# MRCS-ATSN.net
KiCad netlist of a schematic drawn in EAGLE
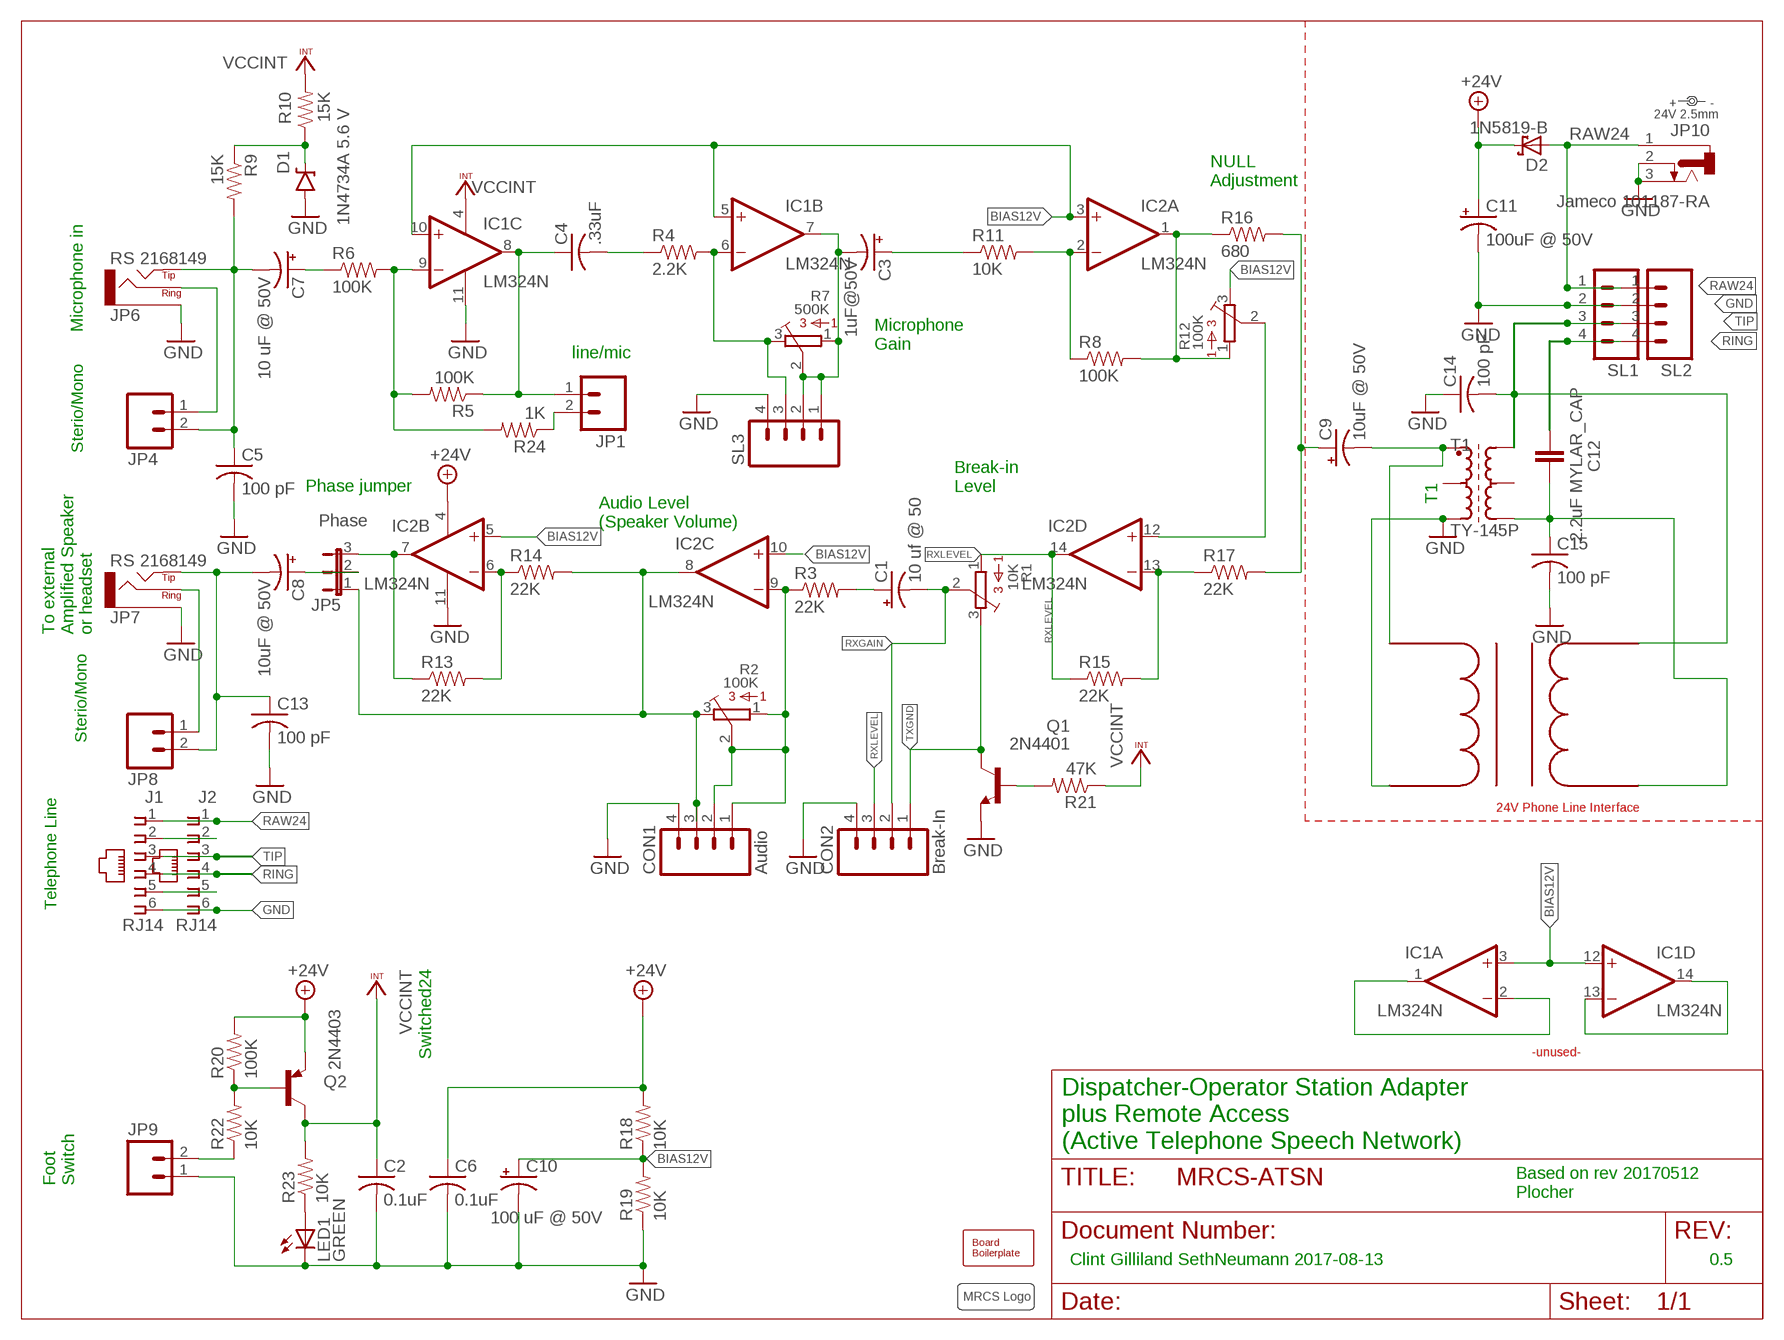
[diagram p0: schematic, sheet 1]

(export (version "E")
  (design (tool "Eeschema 10.0.6"))
  (components
    (comp (ref "BOARD1")
      (value "BOARD69X100")
      (footprint "eagle-import:BOARD-DINRAIL-2.7IN-16CM")
      (libsource (lib "eagle-import") (part "BOARD69X160"))
    )
    (comp (ref "C1")
      (value "10 uf @ 50")
      (footprint "eagle-import:E2-5")
      (libsource (lib "eagle-import") (part "CPOL-USE2-5"))
    )
    (comp (ref "C2")
      (value "0.1uF")
      (footprint "eagle-import:C025-030X050")
      (libsource (lib "eagle-import") (part "C-US025-030X050"))
    )
    (comp (ref "C3")
      (value "1uF@50V")
      (footprint "eagle-import:E2-5")
      (libsource (lib "eagle-import") (part "CPOL-USE2-5"))
    )
    (comp (ref "C4")
      (value ".33uF")
      (footprint "eagle-import:C050-050X075")
      (libsource (lib "eagle-import") (part "C-US050-050X075"))
    )
    (comp (ref "C5")
      (value "100 pF")
      (footprint "eagle-import:C050-025X075")
      (libsource (lib "eagle-import") (part "C-US050-025X075"))
    )
    (comp (ref "C6")
      (value "0.1uF")
      (footprint "eagle-import:C025-030X050")
      (libsource (lib "eagle-import") (part "C-US025-030X050"))
    )
    (comp (ref "C7")
      (value "10 uF @ 50V")
      (footprint "eagle-import:E2-5")
      (libsource (lib "eagle-import") (part "CPOL-USE2-5"))
    )
    (comp (ref "C8")
      (value "10uF @ 50V")
      (footprint "eagle-import:E2-5")
      (libsource (lib "eagle-import") (part "CPOL-USE2-5"))
    )
    (comp (ref "C9")
      (value "10uF @ 50V")
      (footprint "eagle-import:E2-5")
      (libsource (lib "eagle-import") (part "CPOL-USE2-5"))
    )
    (comp (ref "C10")
      (value "100 uF @ 50V")
      (footprint "eagle-import:E3.5-10")
      (libsource (lib "eagle-import") (part "CPOL-USE3.5-10"))
    )
    (comp (ref "C11")
      (value "100uF @ 50V")
      (footprint "eagle-import:E3.5-10")
      (libsource (lib "eagle-import") (part "CPOL-USE3.5-10"))
    )
    (comp (ref "C12")
      (value "2.2uF MYLAR_CAP")
      (footprint "eagle-import:C15B9")
      (libsource (lib "eagle-import") (part "C15/9"))
    )
    (comp (ref "C13")
      (value "100 pF")
      (footprint "eagle-import:C050-025X075")
      (libsource (lib "eagle-import") (part "C-US050-025X075"))
    )
    (comp (ref "C14")
      (value "100 pF")
      (footprint "eagle-import:C025-030X050")
      (libsource (lib "eagle-import") (part "C-US025-030X050"))
    )
    (comp (ref "C15")
      (value "100 pF")
      (footprint "eagle-import:C025-030X050")
      (libsource (lib "eagle-import") (part "C-US025-030X050"))
    )
    (comp (ref "CON1")
      (value "Audio")
      (footprint "eagle-import:1X04_LOCK")
      (libsource (lib "eagle-import") (part "SPCoast 2017_04_CONNECTOR-M04LOCK"))
    )
    (comp (ref "CON2")
      (value "Break-In")
      (footprint "eagle-import:1X04_LOCK")
      (libsource (lib "eagle-import") (part "SPCoast 2017_04_CONNECTOR-M04LOCK"))
    )
    (comp (ref "D1")
      (value "1N4734A 5.6 V")
      (footprint "eagle-import:DIODE-ZENER")
      (libsource (lib "eagle-import") (part "DIODE-ZENERPTH"))
    )
    (comp (ref "D2")
      (value "1N5819-B")
      (footprint "eagle-import:DO41-7.6")
      (libsource (lib "eagle-import") (part "1N5819-B"))
    )
    (comp (ref "IC1")
      (value "LM324N")
      (footprint "eagle-import:DIL14")
      (libsource (lib "eagle-import") (part "LM324N"))
    )
    (comp (ref "IC2")
      (value "LM324N")
      (footprint "eagle-import:DIL14")
      (libsource (lib "eagle-import") (part "LM324N"))
    )
    (comp (ref "J1")
      (value "RJ14")
      (footprint "eagle-import:RJ25-INVERTED")
      (libsource (lib "eagle-import") (part "CONNECTOR-RJ25-43860-2-MOLEX"))
    )
    (comp (ref "J2")
      (value "RJ14")
      (footprint "eagle-import:RJ25-INVERTED")
      (libsource (lib "eagle-import") (part "CONNECTOR-RJ25-43860-2-MOLEX"))
    )
    (comp (ref "JP1")
      (value "CONNECTOR-M021X02-LOCK")
      (footprint "eagle-import:1X02_LOCK")
      (libsource (lib "eagle-import") (part "CONNECTOR-M021X02-LOCK"))
    )
    (comp (ref "JP4")
      (value "CONNECTOR-M021X02-LOCK")
      (footprint "eagle-import:1X02_LOCK")
      (libsource (lib "eagle-import") (part "CONNECTOR-M021X02-LOCK"))
    )
    (comp (ref "JP5")
      (value "Phase")
      (footprint "eagle-import:1X03")
      (libsource (lib "eagle-import") (part "JUMPER-3PTH-LOCK"))
    )
    (comp (ref "JP6")
      (value "RS 2168149")
      (footprint "eagle-import:AUDIO-JACK-3.5MM_STEREO")
      (libsource (lib "eagle-import") (part "CONNECTOR-AUDIO3.5MM-ADAMTECH"))
    )
    (comp (ref "JP7")
      (value "RS 2168149")
      (footprint "eagle-import:AUDIO-JACK-3.5MM_STEREO")
      (libsource (lib "eagle-import") (part "CONNECTOR-AUDIO3.5MM-ADAMTECH"))
    )
    (comp (ref "JP8")
      (value "CONNECTOR-M021X02-LOCK")
      (footprint "eagle-import:1X02_LOCK")
      (libsource (lib "eagle-import") (part "CONNECTOR-M021X02-LOCK"))
    )
    (comp (ref "JP9")
      (value "CONNECTOR-M02508-LOCK")
      (footprint "eagle-import:MSTB2")
      (libsource (lib "eagle-import") (part "CONNECTOR-M02508-LOCK"))
    )
    (comp (ref "JP10")
      (value "Jameco 101187-RA")
      (footprint "eagle-import:DCJ0202")
      (libsource (lib "eagle-import") (part "CONNECTOR-DC-POWER-RA"))
    )
    (comp (ref "LED1")
      (value "GREEN")
      (footprint "eagle-import:LED3MM")
      (libsource (lib "eagle-import") (part "LED3MM"))
    )
    (comp (ref "POWER")
      (value "24V 2.5mm")
      (footprint "eagle-import:POWER_USAGE")
      (libsource (lib "eagle-import") (part "DOC-POWER_LABEL"))
    )
    (comp (ref "Q1")
      (value "2N4401")
      (footprint "eagle-import:TO92-EBC")
      (libsource (lib "eagle-import") (part "-NPN-TO92-EBC29"))
    )
    (comp (ref "Q2")
      (value "2N4403")
      (footprint "eagle-import:TO92-CBE")
      (libsource (lib "eagle-import") (part "2N4126"))
    )
    (comp (ref "R1")
      (value "10K")
      (footprint "eagle-import:3386K")
      (libsource (lib "eagle-import") (part "3386-K"))
    )
    (comp (ref "R2")
      (value "100K")
      (footprint "eagle-import:3386K")
      (libsource (lib "eagle-import") (part "3386-K"))
    )
    (comp (ref "R3")
      (value "22K")
      (footprint "eagle-import:AXIAL-0.4")
      (libsource (lib "eagle-import") (part "RESISTORPTH-1/4W"))
    )
    (comp (ref "R4")
      (value "2.2K")
      (footprint "eagle-import:AXIAL-0.4")
      (libsource (lib "eagle-import") (part "RESISTORPTH-1/4W"))
    )
    (comp (ref "R5")
      (value "100K")
      (footprint "eagle-import:AXIAL-0.4")
      (libsource (lib "eagle-import") (part "RESISTORPTH-1/4W"))
    )
    (comp (ref "R6")
      (value "100K")
      (footprint "eagle-import:AXIAL-0.4")
      (libsource (lib "eagle-import") (part "RESISTORPTH-1/4W"))
    )
    (comp (ref "R7")
      (value "500K")
      (footprint "eagle-import:3386K")
      (libsource (lib "eagle-import") (part "3386-K"))
    )
    (comp (ref "R8")
      (value "100K")
      (footprint "eagle-import:AXIAL-0.4")
      (libsource (lib "eagle-import") (part "RESISTORPTH-1/4W"))
    )
    (comp (ref "R9")
      (value "15K")
      (footprint "eagle-import:AXIAL-0.4")
      (libsource (lib "eagle-import") (part "RESISTORPTH-1/4W"))
    )
    (comp (ref "R10")
      (value "15K")
      (footprint "eagle-import:AXIAL-0.4")
      (libsource (lib "eagle-import") (part "RESISTORPTH-1/4W"))
    )
    (comp (ref "R11")
      (value "10K")
      (footprint "eagle-import:AXIAL-0.4")
      (libsource (lib "eagle-import") (part "RESISTORPTH-1/4W"))
    )
    (comp (ref "R12")
      (value "100K")
      (footprint "eagle-import:3386K")
      (libsource (lib "eagle-import") (part "3386-K"))
    )
    (comp (ref "R13")
      (value "22K")
      (footprint "eagle-import:AXIAL-0.4")
      (libsource (lib "eagle-import") (part "RESISTORPTH-1/4W"))
    )
    (comp (ref "R14")
      (value "22K")
      (footprint "eagle-import:AXIAL-0.4")
      (libsource (lib "eagle-import") (part "RESISTORPTH-1/4W"))
    )
    (comp (ref "R15")
      (value "22K")
      (footprint "eagle-import:AXIAL-0.4")
      (libsource (lib "eagle-import") (part "RESISTORPTH-1/4W"))
    )
    (comp (ref "R16")
      (value "680")
      (footprint "eagle-import:AXIAL-0.4")
      (libsource (lib "eagle-import") (part "RESISTORPTH-1/4W"))
    )
    (comp (ref "R17")
      (value "22K")
      (footprint "eagle-import:AXIAL-0.4")
      (libsource (lib "eagle-import") (part "RESISTORPTH-1/4W"))
    )
    (comp (ref "R18")
      (value "10K")
      (footprint "eagle-import:AXIAL-0.4")
      (libsource (lib "eagle-import") (part "RESISTORPTH-1/4W"))
    )
    (comp (ref "R19")
      (value "10K")
      (footprint "eagle-import:AXIAL-0.4")
      (libsource (lib "eagle-import") (part "RESISTORPTH-1/4W"))
    )
    (comp (ref "R20")
      (value "100K")
      (footprint "eagle-import:AXIAL-0.4")
      (libsource (lib "eagle-import") (part "RESISTORPTH-1/4W"))
    )
    (comp (ref "R21")
      (value "47K")
      (footprint "eagle-import:AXIAL-0.4")
      (libsource (lib "eagle-import") (part "RESISTORPTH-1/4W"))
    )
    (comp (ref "R22")
      (value "10K")
      (footprint "eagle-import:AXIAL-0.4")
      (libsource (lib "eagle-import") (part "RESISTORPTH-1/4W"))
    )
    (comp (ref "R23")
      (value "10K")
      (footprint "eagle-import:AXIAL-0.4")
      (libsource (lib "eagle-import") (part "RESISTORPTH-1/4W"))
    )
    (comp (ref "R24")
      (value "1K")
      (footprint "eagle-import:AXIAL-0.4")
      (libsource (lib "eagle-import") (part "RESISTORPTH-1/4W"))
    )
    (comp (ref "SL1")
      (value "CONNECTOR-M04POLAR_LOCK")
      (footprint "eagle-import:MOLEX-1X4_LOCK")
      (libsource (lib "eagle-import") (part "CONNECTOR-M04POLAR_LOCK"))
    )
    (comp (ref "SL2")
      (value "CONNECTOR-M04POLAR_LOCK")
      (footprint "eagle-import:MOLEX-1X4_LOCK")
      (libsource (lib "eagle-import") (part "CONNECTOR-M04POLAR_LOCK"))
    )
    (comp (ref "SL3")
      (value "CONNECTOR-M04POLAR_LOCK")
      (footprint "eagle-import:MOLEX-1X4_LOCK")
      (libsource (lib "eagle-import") (part "CONNECTOR-M04POLAR_LOCK"))
    )
    (comp (ref "T1")
      (value "TY-145P")
      (footprint "eagle-import:TRANFORMER")
      (libsource (lib "eagle-import") (part "TY-145P"))
    )
    (comp (ref "U$1")
      (value "MRCS-LOGOBOT-LARGE")
      (footprint "eagle-import:MRCS-LOGO")
      (libsource (lib "eagle-import") (part "MRCS-LOGOBOT-LARGE"))
    )
    (comp (ref "U$2")
      (value "EI14_600-600")
      (footprint "eagle-import:XFMR580X500")
      (libsource (lib "eagle-import") (part "EI14_600-600"))
    )
  )
  (nets
    (net (code "1") (name "+24V") (class "Default")
      (node (ref "C11") (pin "+") (pinfunction "+_+") (pintype "passive"))
      (node (ref "C6") (pin "1") (pinfunction "1_1") (pintype "passive"))
      (node (ref "D2") (pin "C") (pinfunction "C_C") (pintype "passive"))
      (node (ref "IC2") (pin "4") (pinfunction "V+_4") (pintype "power_in"))
      (node (ref "Q2") (pin "E") (pinfunction "E_E") (pintype "passive"))
      (node (ref "R18") (pin "P$2") (pinfunction "2_P$2") (pintype "passive"))
      (node (ref "R20") (pin "P$2") (pinfunction "2_P$2") (pintype "passive"))
    )
    (net (code "2") (name "BIAS12V") (class "Default")
      (node (ref "C10") (pin "+") (pinfunction "+_+") (pintype "passive"))
      (node (ref "IC1") (pin "10") (pinfunction "+IN_10") (pintype "input"))
      (node (ref "IC1") (pin "5") (pinfunction "+IN_5") (pintype "input"))
      (node (ref "IC2") (pin "10") (pinfunction "+IN_10") (pintype "input"))
      (node (ref "IC2") (pin "3") (pinfunction "+IN_3") (pintype "input"))
      (node (ref "IC2") (pin "5") (pinfunction "+IN_5") (pintype "input"))
      (node (ref "R12") (pin "3") (pinfunction "3_3") (pintype "passive"))
      (node (ref "R18") (pin "P$1") (pinfunction "1_P$1") (pintype "passive"))
      (node (ref "R19") (pin "P$2") (pinfunction "2_P$2") (pintype "passive"))
    )
    (net (code "3") (name "GND") (class "Default")
      (node (ref "C10") (pin "-") (pinfunction "-_-") (pintype "passive"))
      (node (ref "C11") (pin "-") (pinfunction "-_-") (pintype "passive"))
      (node (ref "C13") (pin "2") (pinfunction "2_2") (pintype "passive"))
      (node (ref "C14") (pin "1") (pinfunction "1_1") (pintype "passive"))
      (node (ref "C15") (pin "2") (pinfunction "2_2") (pintype "passive"))
      (node (ref "C2") (pin "2") (pinfunction "2_2") (pintype "passive"))
      (node (ref "C5") (pin "2") (pinfunction "2_2") (pintype "passive"))
      (node (ref "C6") (pin "2") (pinfunction "2_2") (pintype "passive"))
      (node (ref "CON1") (pin "4") (pinfunction "4_4") (pintype "passive"))
      (node (ref "CON2") (pin "4") (pinfunction "4_4") (pintype "passive"))
      (node (ref "D1") (pin "P$2") (pinfunction "A_P$2") (pintype "passive"))
      (node (ref "IC1") (pin "11") (pinfunction "V-_11") (pintype "power_in"))
      (node (ref "IC2") (pin "11") (pinfunction "V-_11") (pintype "power_in"))
      (node (ref "J1") (pin "6") (pinfunction "6_6") (pintype "passive"))
      (node (ref "J2") (pin "6") (pinfunction "6_6") (pintype "passive"))
      (node (ref "JP10") (pin "2") (pinfunction "2_2") (pintype "passive"))
      (node (ref "JP10") (pin "3") (pinfunction "3_3") (pintype "passive"))
      (node (ref "JP6") (pin "GND") (pinfunction "SLEEVE_GND") (pintype "bidirectional"))
      (node (ref "JP7") (pin "GND") (pinfunction "SLEEVE_GND") (pintype "bidirectional"))
      (node (ref "JP9") (pin "1") (pinfunction "1_1") (pintype "passive"))
      (node (ref "LED1") (pin "K") (pinfunction "C_K") (pintype "passive"))
      (node (ref "Q1") (pin "E") (pinfunction "E_E") (pintype "passive"))
      (node (ref "R19") (pin "P$1") (pinfunction "1_P$1") (pintype "passive"))
      (node (ref "SL1") (pin "2") (pinfunction "2_2") (pintype "passive"))
      (node (ref "SL2") (pin "2") (pinfunction "2_2") (pintype "passive"))
      (node (ref "SL3") (pin "4") (pinfunction "4_4") (pintype "passive"))
      (node (ref "T1") (pin "3") (pinfunction "E1_3") (pintype "passive"))
      (node (ref "U$2") (pin "PBOTTOM") (pinfunction "PBOTTOM_PBOTTOM") (pintype "bidirectional"))
    )
    (net (code "4") (name "Net-(C8-Pad+)") (class "Default")
      (node (ref "C8") (pin "+") (pinfunction "+_+") (pintype "passive"))
      (node (ref "JP5") (pin "2") (pinfunction "2_2") (pintype "passive"))
    )
    (net (code "5") (name "Net-(C13-Pad1)") (class "Default")
      (node (ref "C13") (pin "1") (pinfunction "1_1") (pintype "passive"))
      (node (ref "C8") (pin "-") (pinfunction "-_-") (pintype "passive"))
      (node (ref "JP7") (pin "TIP") (pinfunction "TIP_TIP") (pintype "bidirectional"))
      (node (ref "JP8") (pin "2") (pinfunction "2_2") (pintype "passive"))
    )
    (net (code "6") (name "Net-(D1-C)") (class "Default")
      (node (ref "D1") (pin "P$1") (pinfunction "C_P$1") (pintype "passive"))
      (node (ref "R10") (pin "P$1") (pinfunction "1_P$1") (pintype "passive"))
      (node (ref "R9") (pin "P$1") (pinfunction "1_P$1") (pintype "passive"))
    )
    (net (code "7") (name "Net-(IC1A-+IN)") (class "Default")
      (node (ref "IC1") (pin "12") (pinfunction "+IN_12") (pintype "input"))
      (node (ref "IC1") (pin "3") (pinfunction "+IN_3") (pintype "input"))
    )
    (net (code "8") (name "Net-(IC1A--IN)") (class "Default")
      (node (ref "IC1") (pin "1") (pinfunction "OUT_1") (pintype "output"))
      (node (ref "IC1") (pin "2") (pinfunction "-IN_2") (pintype "input"))
    )
    (net (code "9") (name "Net-(IC1B--IN)") (class "Default")
      (node (ref "IC1") (pin "6") (pinfunction "-IN_6") (pintype "input"))
      (node (ref "R4") (pin "P$2") (pinfunction "2_P$2") (pintype "passive"))
      (node (ref "R7") (pin "3") (pinfunction "3_3") (pintype "passive"))
      (node (ref "SL3") (pin "3") (pinfunction "3_3") (pintype "passive"))
    )
    (net (code "10") (name "Net-(IC1B-OUT)") (class "Default")
      (node (ref "C3") (pin "-") (pinfunction "-_-") (pintype "passive"))
      (node (ref "IC1") (pin "7") (pinfunction "OUT_7") (pintype "output"))
      (node (ref "R7") (pin "1") (pinfunction "1_1") (pintype "passive"))
      (node (ref "R7") (pin "2") (pinfunction "2_2") (pintype "passive"))
      (node (ref "SL3") (pin "1") (pinfunction "1_1") (pintype "passive"))
      (node (ref "SL3") (pin "2") (pinfunction "2_2") (pintype "passive"))
    )
    (net (code "11") (name "Net-(IC1C--IN)") (class "Default")
      (node (ref "IC1") (pin "9") (pinfunction "-IN_9") (pintype "input"))
      (node (ref "R24") (pin "P$2") (pinfunction "2_P$2") (pintype "passive"))
      (node (ref "R5") (pin "P$2") (pinfunction "2_P$2") (pintype "passive"))
      (node (ref "R6") (pin "P$2") (pinfunction "2_P$2") (pintype "passive"))
    )
    (net (code "12") (name "Net-(IC1C-OUT)") (class "Default")
      (node (ref "C4") (pin "1") (pinfunction "1_1") (pintype "passive"))
      (node (ref "IC1") (pin "8") (pinfunction "OUT_8") (pintype "output"))
      (node (ref "JP1") (pin "1") (pinfunction "1_1") (pintype "passive"))
      (node (ref "R5") (pin "P$1") (pinfunction "1_P$1") (pintype "passive"))
    )
    (net (code "13") (name "Net-(IC1D--IN)") (class "Default")
      (node (ref "IC1") (pin "13") (pinfunction "-IN_13") (pintype "input"))
      (node (ref "IC1") (pin "14") (pinfunction "OUT_14") (pintype "output"))
    )
    (net (code "14") (name "Net-(IC2A--IN)") (class "Default")
      (node (ref "IC2") (pin "2") (pinfunction "-IN_2") (pintype "input"))
      (node (ref "R11") (pin "P$2") (pinfunction "2_P$2") (pintype "passive"))
      (node (ref "R8") (pin "P$1") (pinfunction "1_P$1") (pintype "passive"))
    )
    (net (code "15") (name "Net-(IC2A-OUT)") (class "Default")
      (node (ref "IC2") (pin "1") (pinfunction "OUT_1") (pintype "output"))
      (node (ref "R12") (pin "1") (pinfunction "1_1") (pintype "passive"))
      (node (ref "R16") (pin "P$1") (pinfunction "1_P$1") (pintype "passive"))
      (node (ref "R8") (pin "P$2") (pinfunction "2_P$2") (pintype "passive"))
    )
    (net (code "16") (name "Net-(IC2B--IN)") (class "Default")
      (node (ref "IC2") (pin "6") (pinfunction "-IN_6") (pintype "input"))
      (node (ref "R13") (pin "P$2") (pinfunction "2_P$2") (pintype "passive"))
      (node (ref "R14") (pin "P$1") (pinfunction "1_P$1") (pintype "passive"))
    )
    (net (code "17") (name "Net-(IC2B-OUT)") (class "Default")
      (node (ref "IC2") (pin "7") (pinfunction "OUT_7") (pintype "output"))
      (node (ref "JP5") (pin "3") (pinfunction "3_3") (pintype "passive"))
      (node (ref "R13") (pin "P$1") (pinfunction "1_P$1") (pintype "passive"))
    )
    (net (code "18") (name "Net-(IC2C--IN)") (class "Default")
      (node (ref "CON1") (pin "1") (pinfunction "1_1") (pintype "passive"))
      (node (ref "CON1") (pin "2") (pinfunction "2_2") (pintype "passive"))
      (node (ref "IC2") (pin "9") (pinfunction "-IN_9") (pintype "input"))
      (node (ref "R2") (pin "1") (pinfunction "1_1") (pintype "passive"))
      (node (ref "R2") (pin "2") (pinfunction "2_2") (pintype "passive"))
      (node (ref "R3") (pin "P$1") (pinfunction "1_P$1") (pintype "passive"))
    )
    (net (code "19") (name "Net-(IC2C-OUT)") (class "Default")
      (node (ref "CON1") (pin "3") (pinfunction "3_3") (pintype "passive"))
      (node (ref "IC2") (pin "8") (pinfunction "OUT_8") (pintype "output"))
      (node (ref "JP5") (pin "1") (pinfunction "1_1") (pintype "passive"))
      (node (ref "R14") (pin "P$2") (pinfunction "2_P$2") (pintype "passive"))
      (node (ref "R2") (pin "3") (pinfunction "3_3") (pintype "passive"))
    )
    (net (code "20") (name "Net-(IC2D-+IN)") (class "Default")
      (node (ref "IC2") (pin "12") (pinfunction "+IN_12") (pintype "input"))
      (node (ref "R12") (pin "2") (pinfunction "2_2") (pintype "passive"))
    )
    (net (code "21") (name "Net-(IC2D--IN)") (class "Default")
      (node (ref "IC2") (pin "13") (pinfunction "-IN_13") (pintype "input"))
      (node (ref "R15") (pin "P$2") (pinfunction "2_P$2") (pintype "passive"))
      (node (ref "R17") (pin "P$1") (pinfunction "1_P$1") (pintype "passive"))
    )
    (net (code "22") (name "Net-(J1-Pad2)") (class "Default")
      (node (ref "J1") (pin "2") (pinfunction "2_2") (pintype "passive"))
      (node (ref "J2") (pin "2") (pinfunction "2_2") (pintype "passive"))
    )
    (net (code "23") (name "Net-(J1-Pad5)") (class "Default")
      (node (ref "J1") (pin "5") (pinfunction "5_5") (pintype "passive"))
      (node (ref "J2") (pin "5") (pinfunction "5_5") (pintype "passive"))
    )
    (net (code "24") (name "Net-(JP4-Pad1)") (class "Default")
      (node (ref "JP4") (pin "1") (pinfunction "1_1") (pintype "passive"))
      (node (ref "JP6") (pin "RING") (pinfunction "RING_RING") (pintype "bidirectional"))
    )
    (net (code "25") (name "Net-(JP7-PadRING)") (class "Default")
      (node (ref "JP7") (pin "RING") (pinfunction "RING_RING") (pintype "bidirectional"))
      (node (ref "JP8") (pin "1") (pinfunction "1_1") (pintype "passive"))
    )
    (net (code "26") (name "Net-(R3-2)") (class "Default")
      (node (ref "C1") (pin "+") (pinfunction "+_+") (pintype "passive"))
      (node (ref "R3") (pin "P$2") (pinfunction "2_P$2") (pintype "passive"))
    )
    (net (code "27") (name "Net-(R4-1)") (class "Default")
      (node (ref "C4") (pin "2") (pinfunction "2_2") (pintype "passive"))
      (node (ref "R4") (pin "P$1") (pinfunction "1_P$1") (pintype "passive"))
    )
    (net (code "28") (name "Net-(R6-1)") (class "Default")
      (node (ref "C7") (pin "+") (pinfunction "+_+") (pintype "passive"))
      (node (ref "R6") (pin "P$1") (pinfunction "1_P$1") (pintype "passive"))
    )
    (net (code "29") (name "Net-(R9-2)") (class "Default")
      (node (ref "C5") (pin "1") (pinfunction "1_1") (pintype "passive"))
      (node (ref "C7") (pin "-") (pinfunction "-_-") (pintype "passive"))
      (node (ref "JP4") (pin "2") (pinfunction "2_2") (pintype "passive"))
      (node (ref "JP6") (pin "TIP") (pinfunction "TIP_TIP") (pintype "bidirectional"))
      (node (ref "R9") (pin "P$2") (pinfunction "2_P$2") (pintype "passive"))
    )
    (net (code "30") (name "Net-(R11-1)") (class "Default")
      (node (ref "C3") (pin "+") (pinfunction "+_+") (pintype "passive"))
      (node (ref "R11") (pin "P$1") (pinfunction "1_P$1") (pintype "passive"))
    )
    (net (code "31") (name "Net-(R16-2)") (class "Default")
      (node (ref "C9") (pin "+") (pinfunction "+_+") (pintype "passive"))
      (node (ref "R16") (pin "P$2") (pinfunction "2_P$2") (pintype "passive"))
      (node (ref "R17") (pin "P$2") (pinfunction "2_P$2") (pintype "passive"))
    )
    (net (code "32") (name "Net-(R20-1)") (class "Default")
      (node (ref "Q2") (pin "B") (pinfunction "B_B") (pintype "passive"))
      (node (ref "R20") (pin "P$1") (pinfunction "1_P$1") (pintype "passive"))
      (node (ref "R22") (pin "P$2") (pinfunction "2_P$2") (pintype "passive"))
    )
    (net (code "33") (name "Net-(R21-2)") (class "Default")
      (node (ref "Q1") (pin "B") (pinfunction "B_B") (pintype "passive"))
      (node (ref "R21") (pin "P$2") (pinfunction "2_P$2") (pintype "passive"))
    )
    (net (code "34") (name "Net-(R22-1)") (class "Default")
      (node (ref "JP9") (pin "2") (pinfunction "2_2") (pintype "passive"))
      (node (ref "R22") (pin "P$1") (pinfunction "1_P$1") (pintype "passive"))
    )
    (net (code "35") (name "Net-(R23-1)") (class "Default")
      (node (ref "LED1") (pin "A") (pinfunction "A_A") (pintype "passive"))
      (node (ref "R23") (pin "P$1") (pinfunction "1_P$1") (pintype "passive"))
    )
    (net (code "36") (name "Net-(R24-1)") (class "Default")
      (node (ref "JP1") (pin "2") (pinfunction "2_2") (pintype "passive"))
      (node (ref "R24") (pin "P$1") (pinfunction "1_P$1") (pintype "passive"))
    )
    (net (code "37") (name "Net-(T1-A1)") (class "Default")
      (node (ref "C9") (pin "-") (pinfunction "-_-") (pintype "passive"))
      (node (ref "T1") (pin "1") (pinfunction "A1_1") (pintype "passive"))
      (node (ref "U$2") (pin "PTOP") (pinfunction "PTOP_PTOP") (pintype "bidirectional"))
    )
    (net (code "38") (name "Net-(T1-E2)") (class "Default")
      (node (ref "C12") (pin "1") (pinfunction "1_1") (pintype "passive"))
      (node (ref "C15") (pin "1") (pinfunction "1_1") (pintype "passive"))
      (node (ref "T1") (pin "4") (pinfunction "E2_4") (pintype "passive"))
      (node (ref "U$2") (pin "SBOTTOM") (pinfunction "SBOTTOM_SBOTTOM") (pintype "bidirectional"))
    )
    (net (code "39") (name "RAW24") (class "Default")
      (node (ref "D2") (pin "A") (pinfunction "A_A") (pintype "passive"))
      (node (ref "J1") (pin "1") (pinfunction "1_1") (pintype "passive"))
      (node (ref "J2") (pin "1") (pinfunction "1_1") (pintype "passive"))
      (node (ref "JP10") (pin "1") (pinfunction "1_1") (pintype "passive"))
      (node (ref "SL1") (pin "1") (pinfunction "1_1") (pintype "passive"))
      (node (ref "SL2") (pin "1") (pinfunction "1_1") (pintype "passive"))
    )
    (net (code "40") (name "RING") (class "Default")
      (node (ref "C12") (pin "2") (pinfunction "2_2") (pintype "passive"))
      (node (ref "J1") (pin "4") (pinfunction "4_4") (pintype "passive"))
      (node (ref "J2") (pin "4") (pinfunction "4_4") (pintype "passive"))
      (node (ref "SL1") (pin "4") (pinfunction "4_4") (pintype "passive"))
      (node (ref "SL2") (pin "4") (pinfunction "4_4") (pintype "passive"))
    )
    (net (code "41") (name "RXGAIN") (class "Default")
      (node (ref "C1") (pin "-") (pinfunction "-_-") (pintype "passive"))
      (node (ref "CON2") (pin "2") (pinfunction "2_2") (pintype "passive"))
      (node (ref "R1") (pin "2") (pinfunction "2_2") (pintype "passive"))
    )
    (net (code "42") (name "RXLEVEL") (class "Default")
      (node (ref "CON2") (pin "3") (pinfunction "3_3") (pintype "passive"))
      (node (ref "IC2") (pin "14") (pinfunction "OUT_14") (pintype "output"))
      (node (ref "R1") (pin "1") (pinfunction "1_1") (pintype "passive"))
      (node (ref "R15") (pin "P$1") (pinfunction "1_P$1") (pintype "passive"))
    )
    (net (code "43") (name "TIP") (class "Default")
      (node (ref "C14") (pin "2") (pinfunction "2_2") (pintype "passive"))
      (node (ref "J1") (pin "3") (pinfunction "3_3") (pintype "passive"))
      (node (ref "J2") (pin "3") (pinfunction "3_3") (pintype "passive"))
      (node (ref "SL1") (pin "3") (pinfunction "3_3") (pintype "passive"))
      (node (ref "SL2") (pin "3") (pinfunction "3_3") (pintype "passive"))
      (node (ref "T1") (pin "6") (pinfunction "A2_6") (pintype "passive"))
      (node (ref "U$2") (pin "STOP") (pinfunction "STOP_STOP") (pintype "bidirectional"))
    )
    (net (code "44") (name "TXGND") (class "Default")
      (node (ref "CON2") (pin "1") (pinfunction "1_1") (pintype "passive"))
      (node (ref "Q1") (pin "C") (pinfunction "C_C") (pintype "passive"))
      (node (ref "R1") (pin "3") (pinfunction "3_3") (pintype "passive"))
    )
    (net (code "45") (name "VCCINT") (class "Default")
      (node (ref "C2") (pin "1") (pinfunction "1_1") (pintype "passive"))
      (node (ref "IC1") (pin "4") (pinfunction "V+_4") (pintype "power_in"))
      (node (ref "Q2") (pin "C") (pinfunction "C_C") (pintype "passive"))
      (node (ref "R10") (pin "P$2") (pinfunction "2_P$2") (pintype "passive"))
      (node (ref "R21") (pin "P$1") (pinfunction "1_P$1") (pintype "passive"))
      (node (ref "R23") (pin "P$2") (pinfunction "2_P$2") (pintype "passive"))
    )
    (net (code "46") (name "unconnected-(T1-C1-Pad2)") (class "Default")
      (node (ref "T1") (pin "2") (pinfunction "C1_2") (pintype "passive"))
    )
    (net (code "47") (name "unconnected-(T1-C2-Pad5)") (class "Default")
      (node (ref "T1") (pin "5") (pinfunction "C2_5") (pintype "passive"))
    )
  )
)
